# SmartThermo1_9.net
KiCad netlist of a schematic drawn in EAGLE
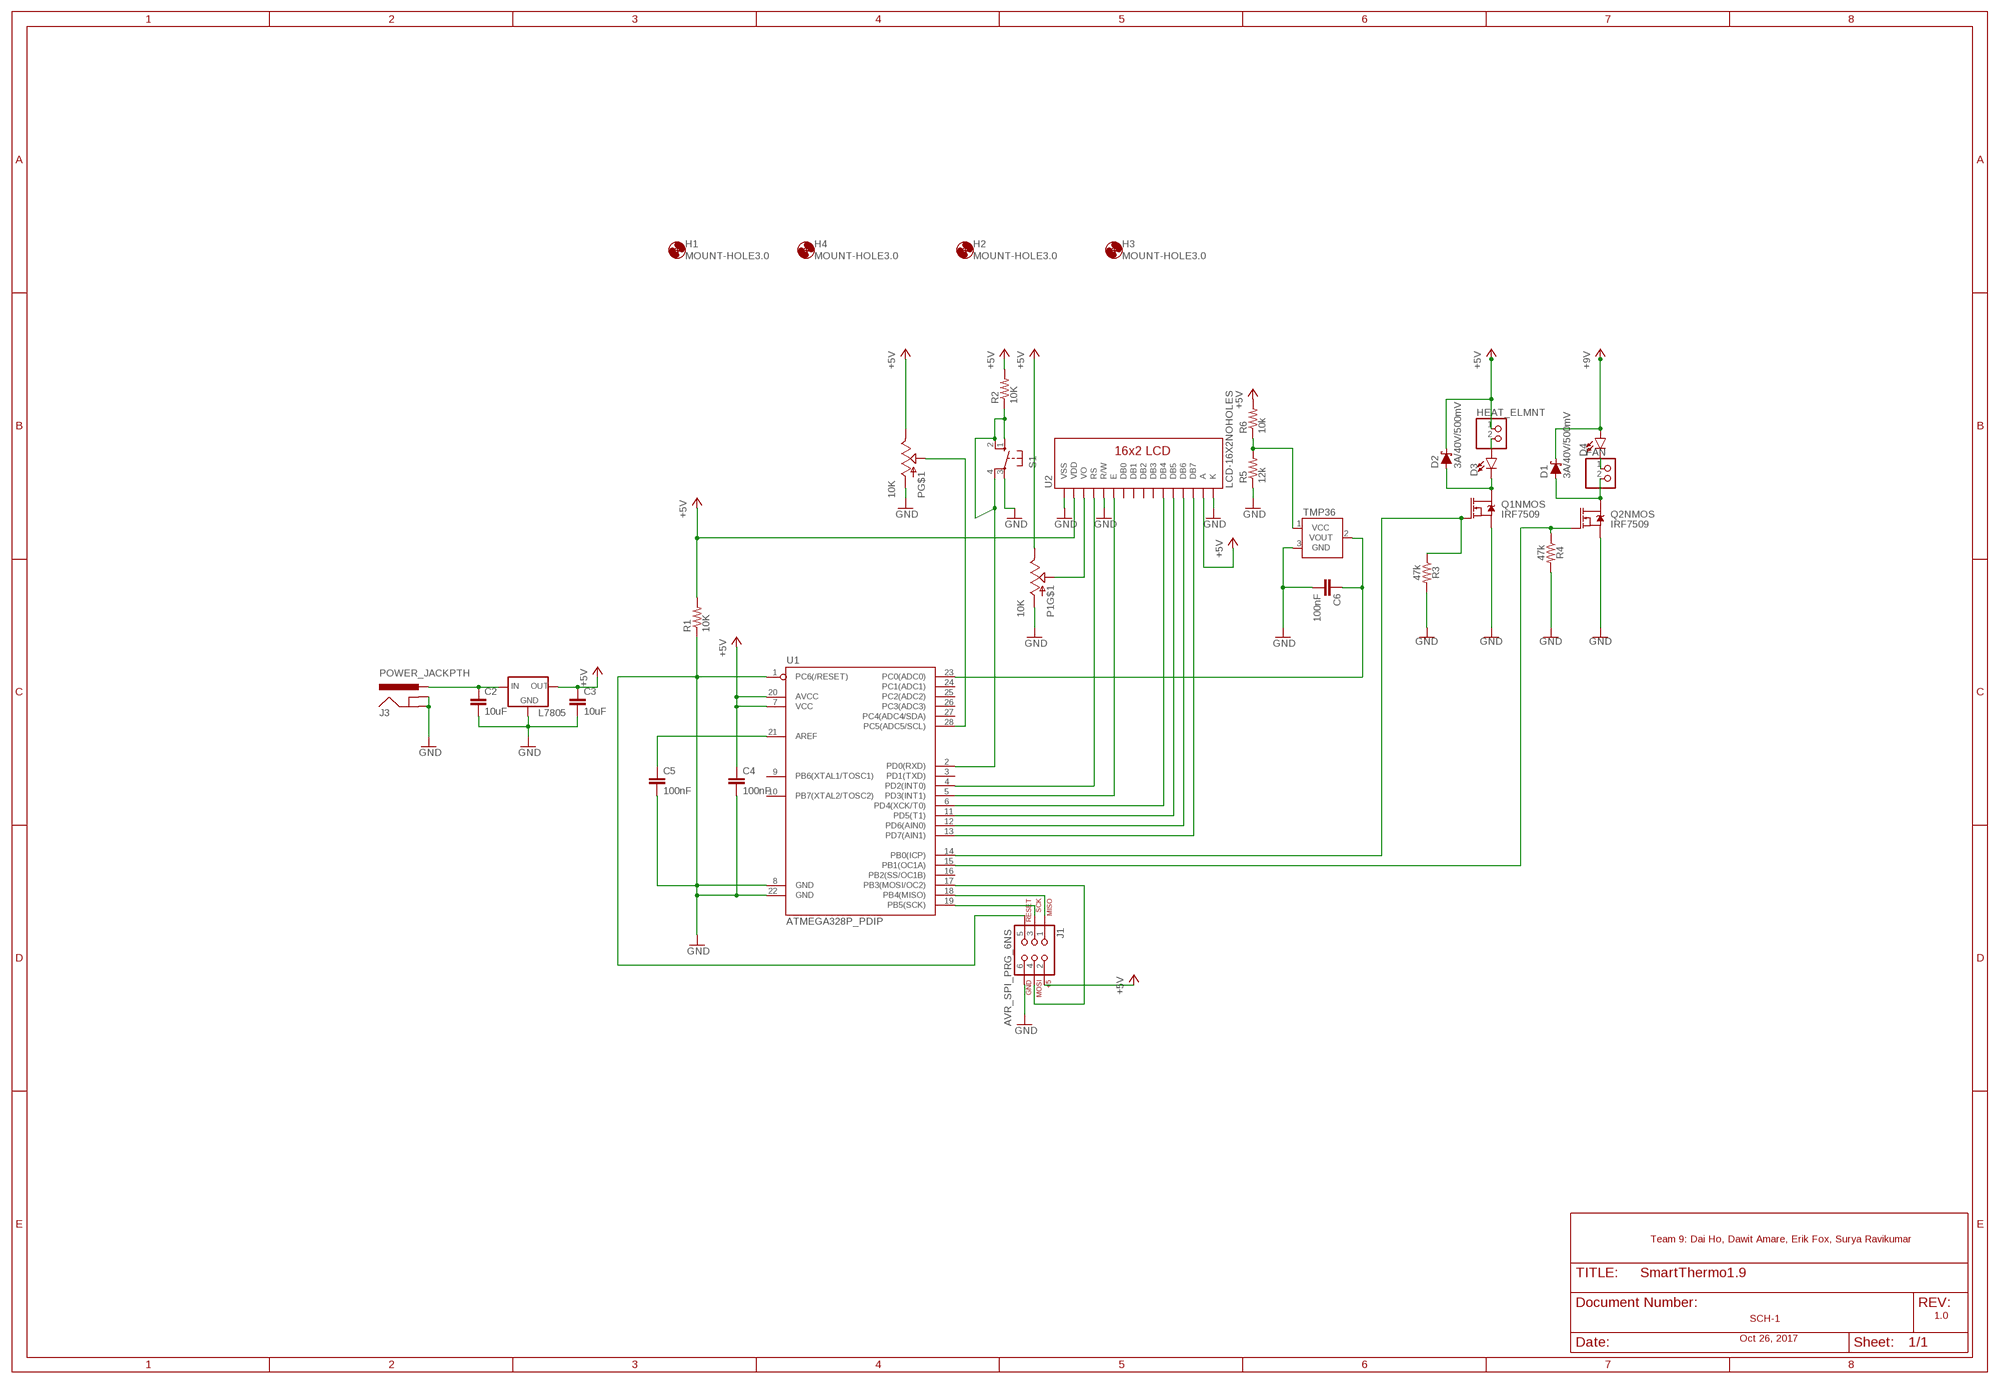
[diagram p0: schematic, sheet 1]

(export (version "E")
  (design (tool "Eeschema 10.0.6"))
  (components
    (comp (ref "C2")
      (value "10uF")
      (footprint "eagle-import:C7.5B3")
      (libsource (lib "eagle-import") (part "C7.5/3"))
    )
    (comp (ref "C3")
      (value "10uF")
      (footprint "eagle-import:C7.5B3")
      (libsource (lib "eagle-import") (part "C7.5/3"))
    )
    (comp (ref "C4")
      (value "100nF")
      (footprint "eagle-import:C2.5-2")
      (libsource (lib "eagle-import") (part "C2.5/2"))
    )
    (comp (ref "C5")
      (value "100nF")
      (footprint "eagle-import:C2.5-2")
      (libsource (lib "eagle-import") (part "C2.5/2"))
    )
    (comp (ref "C6")
      (value "100nF")
      (footprint "eagle-import:C2.5-2")
      (libsource (lib "eagle-import") (part "C2.5/2"))
    )
    (comp (ref "D1")
      (value "3A/40V/500mV")
      (footprint "eagle-import:SMA-DIODE")
      (libsource (lib "eagle-import") (part "DIODE-SCHOTTKY-B340A"))
    )
    (comp (ref "D2")
      (value "3A/40V/500mV")
      (footprint "eagle-import:SMA-DIODE")
      (libsource (lib "eagle-import") (part "DIODE-SCHOTTKY-B340A"))
    )
    (comp (ref "D3")
      (value "LED3MM")
      (footprint "eagle-import:LED_3MM")
      (libsource (lib "eagle-import") (part "LED3MM"))
    )
    (comp (ref "D4")
      (value "LED3MM")
      (footprint "eagle-import:LED_3MM")
      (libsource (lib "eagle-import") (part "LED3MM"))
    )
    (comp (ref "FAN")
      (value "PINHD-1X2/90")
      (footprint "eagle-import:1X02_90")
      (libsource (lib "eagle-import") (part "PINHD-1X2/90"))
    )
    (comp (ref "H1")
      (value "MOUNT-HOLE3.0")
      (footprint "eagle-import:3,0")
      (libsource (lib "eagle-import") (part "MOUNT-HOLE3.0"))
    )
    (comp (ref "H2")
      (value "MOUNT-HOLE3.0")
      (footprint "eagle-import:3,0")
      (libsource (lib "eagle-import") (part "MOUNT-HOLE3.0"))
    )
    (comp (ref "H3")
      (value "MOUNT-HOLE3.0")
      (footprint "eagle-import:3,0")
      (libsource (lib "eagle-import") (part "MOUNT-HOLE3.0"))
    )
    (comp (ref "H4")
      (value "MOUNT-HOLE3.0")
      (footprint "eagle-import:3,0")
      (libsource (lib "eagle-import") (part "MOUNT-HOLE3.0"))
    )
    (comp (ref "HEAT_ELMNT")
      (value "PINHD-1X2/90")
      (footprint "eagle-import:1X02_90")
      (libsource (lib "eagle-import") (part "PINHD-1X2/90"))
    )
    (comp (ref "J1")
      (value "AVR_SPI_PRG_6NS")
      (footprint "eagle-import:2X3-NS")
      (libsource (lib "eagle-import") (part "AVR_SPI_PRG_6NS"))
    )
    (comp (ref "J3")
      (value "POWER_JACKPTH")
      (footprint "eagle-import:POWER_JACK_PTH")
      (libsource (lib "eagle-import") (part "POWER_JACKPTH"))
    )
    (comp (ref "L7805")
      (value "78XXL")
      (footprint "eagle-import:78XXL")
      (libsource (lib "eagle-import") (part "78XXL"))
    )
    (comp (ref "P")
      (value "10K")
      (footprint "eagle-import:POT_PTH")
      (libsource (lib "eagle-import") (part "POT_SWITCHPOT_PTH"))
    )
    (comp (ref "P1")
      (value "10K")
      (footprint "eagle-import:POT_PTH")
      (libsource (lib "eagle-import") (part "POT_SWITCHPOT_PTH"))
    )
    (comp (ref "Q1")
      (value "IRF7509")
      (footprint "eagle-import:MSOP8")
      (libsource (lib "eagle-import") (part "IRF7509"))
    )
    (comp (ref "Q2")
      (value "IRF7509")
      (footprint "eagle-import:MSOP8")
      (libsource (lib "eagle-import") (part "IRF7509"))
    )
    (comp (ref "R1")
      (value "10K")
      (footprint "eagle-import:1206")
      (libsource (lib "eagle-import") (part "RESISTOR1206"))
    )
    (comp (ref "R2")
      (value "10K")
      (footprint "eagle-import:1206")
      (libsource (lib "eagle-import") (part "RESISTOR1206"))
    )
    (comp (ref "R3")
      (value "47k")
      (footprint "eagle-import:0603")
      (libsource (lib "eagle-import") (part "47KOHM-0603-1/10W-1%"))
    )
    (comp (ref "R4")
      (value "47k")
      (footprint "eagle-import:0603")
      (libsource (lib "eagle-import") (part "47KOHM-0603-1/10W-1%"))
    )
    (comp (ref "R5")
      (value "12k")
      (footprint "eagle-import:0204_5")
      (libsource (lib "eagle-import") (part "R-US_0204/5"))
    )
    (comp (ref "R6")
      (value "10k")
      (footprint "eagle-import:0204_5")
      (libsource (lib "eagle-import") (part "R-US_0204/5"))
    )
    (comp (ref "S1")
      (value "10-XX")
      (footprint "eagle-import:B3F-10XX")
      (fields (field (name "MPN") "B3F-1000"))
      (libsource (lib "eagle-import") (part "10-XX"))
    )
    (comp (ref "TMP36")
      (value "TMP36GT9")
      (footprint "eagle-import:TO-92")
      (libsource (lib "eagle-import") (part "TMP36GT9"))
    )
    (comp (ref "U1")
      (value "ATMEGA328P_PDIP")
      (footprint "eagle-import:DIL28-3")
      (libsource (lib "eagle-import") (part "ATMEGA328P_PDIP"))
    )
    (comp (ref "U2")
      (value "LCD-16X2NOHOLES")
      (footprint "eagle-import:LCD-16X2_NOHOLES")
      (libsource (lib "eagle-import") (part "LCD-16X2NOHOLES"))
    )
  )
  (nets
    (net (code "1") (name "+5V") (class "Default")
      (node (ref "C3") (pin "1") (pinfunction "1_1") (pintype "passive"))
      (node (ref "C4") (pin "1") (pinfunction "1_1") (pintype "passive"))
      (node (ref "D1") (pin "C") (pinfunction "C_C") (pintype "passive"))
      (node (ref "D2") (pin "C") (pinfunction "C_C") (pintype "passive"))
      (node (ref "D4") (pin "A") (pinfunction "A_A") (pintype "passive"))
      (node (ref "HEAT_ELMNT") (pin "1") (pinfunction "1_1") (pintype "passive"))
      (node (ref "J1") (pin "2") (pinfunction "2_2") (pintype "passive"))
      (node (ref "L7805") (pin "OUT") (pinfunction "OUT_OUT") (pintype "passive"))
      (node (ref "P") (pin "E@2") (pinfunction "E_E@2") (pintype "passive"))
      (node (ref "P1") (pin "E@2") (pinfunction "E_E@2") (pintype "passive"))
      (node (ref "R1") (pin "2") (pinfunction "2_2") (pintype "passive"))
      (node (ref "R2") (pin "2") (pinfunction "2_2") (pintype "passive"))
      (node (ref "R6") (pin "2") (pinfunction "2_2") (pintype "passive"))
      (node (ref "U1") (pin "20") (pinfunction "AVCC_20") (pintype "bidirectional"))
      (node (ref "U1") (pin "7") (pinfunction "VCC_7") (pintype "bidirectional"))
      (node (ref "U2") (pin "15") (pinfunction "A_15") (pintype "power_in"))
      (node (ref "U2") (pin "2") (pinfunction "VDD_2") (pintype "power_in"))
    )
    (net (code "2") (name "GND") (class "Default")
      (node (ref "C2") (pin "2") (pinfunction "2_2") (pintype "passive"))
      (node (ref "C3") (pin "2") (pinfunction "2_2") (pintype "passive"))
      (node (ref "C4") (pin "2") (pinfunction "2_2") (pintype "passive"))
      (node (ref "C5") (pin "2") (pinfunction "2_2") (pintype "passive"))
      (node (ref "C6") (pin "2") (pinfunction "2_2") (pintype "passive"))
      (node (ref "J1") (pin "5") (pinfunction "5_5") (pintype "passive"))
      (node (ref "J1") (pin "6") (pinfunction "6_6") (pintype "passive"))
      (node (ref "J3") (pin "GND") (pinfunction "GND_GND") (pintype "bidirectional"))
      (node (ref "J3") (pin "GNDBREAK") (pinfunction "GNDBREAK_GNDBREAK") (pintype "bidirectional"))
      (node (ref "L7805") (pin "GND") (pinfunction "GND_GND") (pintype "input"))
      (node (ref "P") (pin "E@1") (pinfunction "A_E@1") (pintype "passive"))
      (node (ref "P1") (pin "E@1") (pinfunction "A_E@1") (pintype "passive"))
      (node (ref "Q1") (pin "1") (pinfunction "S_1") (pintype "bidirectional"))
      (node (ref "Q2") (pin "1") (pinfunction "S_1") (pintype "bidirectional"))
      (node (ref "R1") (pin "1") (pinfunction "1_1") (pintype "passive"))
      (node (ref "R3") (pin "2") (pinfunction "2_2") (pintype "passive"))
      (node (ref "R4") (pin "2") (pinfunction "2_2") (pintype "passive"))
      (node (ref "R5") (pin "1") (pinfunction "1_1") (pintype "passive"))
      (node (ref "S1") (pin "3") (pinfunction "P_3") (pintype "passive"))
      (node (ref "TMP36") (pin "3") (pinfunction "GND_3") (pintype "bidirectional"))
      (node (ref "U1") (pin "1") (pinfunction "PC6(/RESET)_1") (pintype "bidirectional"))
      (node (ref "U1") (pin "22") (pinfunction "GND_22") (pintype "bidirectional"))
      (node (ref "U1") (pin "8") (pinfunction "GND_8") (pintype "bidirectional"))
      (node (ref "U2") (pin "1") (pinfunction "VSS_1") (pintype "power_in"))
      (node (ref "U2") (pin "16") (pinfunction "K_16") (pintype "power_in"))
      (node (ref "U2") (pin "5") (pinfunction "R/W_5") (pintype "input"))
    )
    (net (code "3") (name "Net-(C2-Pad1)") (class "Default")
      (node (ref "C2") (pin "1") (pinfunction "1_1") (pintype "passive"))
      (node (ref "J3") (pin "PWR") (pinfunction "PWR_PWR") (pintype "bidirectional"))
      (node (ref "L7805") (pin "IN") (pinfunction "IN_IN") (pintype "input"))
    )
    (net (code "4") (name "Net-(D1-PadA)") (class "Default")
      (node (ref "D1") (pin "A") (pinfunction "A_A") (pintype "passive"))
      (node (ref "FAN") (pin "2") (pinfunction "2_2") (pintype "passive"))
      (node (ref "Q2") (pin "7") (pinfunction "D_7") (pintype "bidirectional"))
      (node (ref "Q2") (pin "8") (pinfunction "D_8") (pintype "bidirectional"))
    )
    (net (code "5") (name "Net-(D3-C)") (class "Default")
      (node (ref "D2") (pin "A") (pinfunction "A_A") (pintype "passive"))
      (node (ref "D3") (pin "K") (pinfunction "C_K") (pintype "passive"))
      (node (ref "Q1") (pin "7") (pinfunction "D_7") (pintype "bidirectional"))
      (node (ref "Q1") (pin "8") (pinfunction "D_8") (pintype "bidirectional"))
    )
    (net (code "6") (name "Net-(D3-PadA)") (class "Default")
      (node (ref "D3") (pin "A") (pinfunction "A_A") (pintype "passive"))
      (node (ref "HEAT_ELMNT") (pin "2") (pinfunction "2_2") (pintype "passive"))
    )
    (net (code "7") (name "Net-(D4-C)") (class "Default")
      (node (ref "D4") (pin "K") (pinfunction "C_K") (pintype "passive"))
      (node (ref "FAN") (pin "1") (pinfunction "1_1") (pintype "passive"))
    )
    (net (code "8") (name "Net-(P1A-S)") (class "Default")
      (node (ref "P1") (pin "WAND") (pinfunction "S_WAND") (pintype "passive"))
      (node (ref "U2") (pin "3") (pinfunction "VO_3") (pintype "bidirectional"))
    )
    (net (code "9") (name "Net-(PA-S)") (class "Default")
      (node (ref "P") (pin "WAND") (pinfunction "S_WAND") (pintype "passive"))
      (node (ref "U1") (pin "28") (pinfunction "PC5(ADC5/SCL)_28") (pintype "bidirectional"))
    )
    (net (code "10") (name "Net-(Q1A-G)") (class "Default")
      (node (ref "Q1") (pin "2") (pinfunction "G_2") (pintype "bidirectional"))
      (node (ref "R3") (pin "1") (pinfunction "1_1") (pintype "passive"))
      (node (ref "U1") (pin "14") (pinfunction "PB0(ICP)_14") (pintype "bidirectional"))
    )
    (net (code "11") (name "Net-(Q2A-G)") (class "Default")
      (node (ref "Q2") (pin "2") (pinfunction "G_2") (pintype "bidirectional"))
      (node (ref "R4") (pin "1") (pinfunction "1_1") (pintype "passive"))
      (node (ref "U1") (pin "15") (pinfunction "PB1(OC1A)_15") (pintype "bidirectional"))
    )
    (net (code "12") (name "Net-(S1-P1)") (class "Default")
      (node (ref "R2") (pin "1") (pinfunction "1_1") (pintype "passive"))
      (node (ref "S1") (pin "1") (pinfunction "S_1") (pintype "passive"))
      (node (ref "S1") (pin "2") (pinfunction "S1_2") (pintype "passive"))
      (node (ref "S1") (pin "4") (pinfunction "P1_4") (pintype "passive"))
      (node (ref "U1") (pin "2") (pinfunction "PD0(RXD)_2") (pintype "bidirectional"))
    )
    (net (code "13") (name "Net-(TMP36-VCC)") (class "Default")
      (node (ref "R5") (pin "2") (pinfunction "2_2") (pintype "passive"))
      (node (ref "R6") (pin "1") (pinfunction "1_1") (pintype "passive"))
      (node (ref "TMP36") (pin "1") (pinfunction "VCC_1") (pintype "bidirectional"))
    )
    (net (code "14") (name "Net-(TMP36-VOUT)") (class "Default")
      (node (ref "C6") (pin "1") (pinfunction "1_1") (pintype "passive"))
      (node (ref "TMP36") (pin "2") (pinfunction "VOUT_2") (pintype "bidirectional"))
      (node (ref "U1") (pin "23") (pinfunction "PC0(ADC0)_23") (pintype "bidirectional"))
    )
    (net (code "15") (name "Net-(U1-AREF)") (class "Default")
      (node (ref "C5") (pin "1") (pinfunction "1_1") (pintype "passive"))
      (node (ref "U1") (pin "21") (pinfunction "AREF_21") (pintype "bidirectional"))
    )
    (net (code "16") (name "Net-(U1-PB3(MOSI{slash}OC2))") (class "Default")
      (node (ref "J1") (pin "4") (pinfunction "4_4") (pintype "passive"))
      (node (ref "U1") (pin "17") (pinfunction "PB3(MOSI/OC2)_17") (pintype "bidirectional"))
    )
    (net (code "17") (name "Net-(U1-PB4(MISO))") (class "Default")
      (node (ref "J1") (pin "1") (pinfunction "1_1") (pintype "passive"))
      (node (ref "U1") (pin "18") (pinfunction "PB4(MISO)_18") (pintype "bidirectional"))
    )
    (net (code "18") (name "Net-(U1-PB5(SCK))") (class "Default")
      (node (ref "J1") (pin "3") (pinfunction "3_3") (pintype "passive"))
      (node (ref "U1") (pin "19") (pinfunction "PB5(SCK)_19") (pintype "bidirectional"))
    )
    (net (code "19") (name "Net-(U1-PD2(INT0))") (class "Default")
      (node (ref "U1") (pin "4") (pinfunction "PD2(INT0)_4") (pintype "bidirectional"))
      (node (ref "U2") (pin "4") (pinfunction "RS_4") (pintype "input"))
    )
    (net (code "20") (name "Net-(U1-PD3(INT1))") (class "Default")
      (node (ref "U1") (pin "5") (pinfunction "PD3(INT1)_5") (pintype "bidirectional"))
      (node (ref "U2") (pin "6") (pinfunction "E_6") (pintype "input"))
    )
    (net (code "21") (name "Net-(U1-PD4(XCK{slash}T0))") (class "Default")
      (node (ref "U1") (pin "6") (pinfunction "PD4(XCK/T0)_6") (pintype "bidirectional"))
      (node (ref "U2") (pin "11") (pinfunction "DB4_11") (pintype "bidirectional"))
    )
    (net (code "22") (name "Net-(U1-PD5(T1))") (class "Default")
      (node (ref "U1") (pin "11") (pinfunction "PD5(T1)_11") (pintype "bidirectional"))
      (node (ref "U2") (pin "12") (pinfunction "DB5_12") (pintype "bidirectional"))
    )
    (net (code "23") (name "Net-(U1-PD6(AIN0))") (class "Default")
      (node (ref "U1") (pin "12") (pinfunction "PD6(AIN0)_12") (pintype "bidirectional"))
      (node (ref "U2") (pin "13") (pinfunction "DB6_13") (pintype "bidirectional"))
    )
    (net (code "24") (name "Net-(U1-PD7(AIN1))") (class "Default")
      (node (ref "U1") (pin "13") (pinfunction "PD7(AIN1)_13") (pintype "bidirectional"))
      (node (ref "U2") (pin "14") (pinfunction "DB7_14") (pintype "bidirectional"))
    )
    (net (code "25") (name "unconnected-(U1-PB2(SS{slash}OC1B)-Pad16)") (class "Default")
      (node (ref "U1") (pin "16") (pinfunction "PB2(SS/OC1B)_16") (pintype "bidirectional"))
    )
    (net (code "26") (name "unconnected-(U1-PB6(XTAL1{slash}TOSC1)-Pad9)") (class "Default")
      (node (ref "U1") (pin "9") (pinfunction "PB6(XTAL1/TOSC1)_9") (pintype "bidirectional"))
    )
    (net (code "27") (name "unconnected-(U1-PB7(XTAL2{slash}TOSC2)-Pad10)") (class "Default")
      (node (ref "U1") (pin "10") (pinfunction "PB7(XTAL2/TOSC2)_10") (pintype "bidirectional"))
    )
    (net (code "28") (name "unconnected-(U1-PC1(ADC1)-Pad24)") (class "Default")
      (node (ref "U1") (pin "24") (pinfunction "PC1(ADC1)_24") (pintype "bidirectional"))
    )
    (net (code "29") (name "unconnected-(U1-PC2(ADC2)-Pad25)") (class "Default")
      (node (ref "U1") (pin "25") (pinfunction "PC2(ADC2)_25") (pintype "bidirectional"))
    )
    (net (code "30") (name "unconnected-(U1-PC3(ADC3)-Pad26)") (class "Default")
      (node (ref "U1") (pin "26") (pinfunction "PC3(ADC3)_26") (pintype "bidirectional"))
    )
    (net (code "31") (name "unconnected-(U1-PC4(ADC4{slash}SDA)-Pad27)") (class "Default")
      (node (ref "U1") (pin "27") (pinfunction "PC4(ADC4/SDA)_27") (pintype "bidirectional"))
    )
    (net (code "32") (name "unconnected-(U1-PD1(TXD)-Pad3)") (class "Default")
      (node (ref "U1") (pin "3") (pinfunction "PD1(TXD)_3") (pintype "bidirectional"))
    )
    (net (code "33") (name "unconnected-(U2-DB0-Pad7)") (class "Default")
      (node (ref "U2") (pin "7") (pinfunction "DB0_7") (pintype "bidirectional"))
    )
    (net (code "34") (name "unconnected-(U2-DB1-Pad8)") (class "Default")
      (node (ref "U2") (pin "8") (pinfunction "DB1_8") (pintype "bidirectional"))
    )
    (net (code "35") (name "unconnected-(U2-DB2-Pad9)") (class "Default")
      (node (ref "U2") (pin "9") (pinfunction "DB2_9") (pintype "bidirectional"))
    )
    (net (code "36") (name "unconnected-(U2-DB3-Pad10)") (class "Default")
      (node (ref "U2") (pin "10") (pinfunction "DB3_10") (pintype "bidirectional"))
    )
  )
)
